# Processing_Unit.net
KiCad netlist of a schematic drawn in Altium Designer
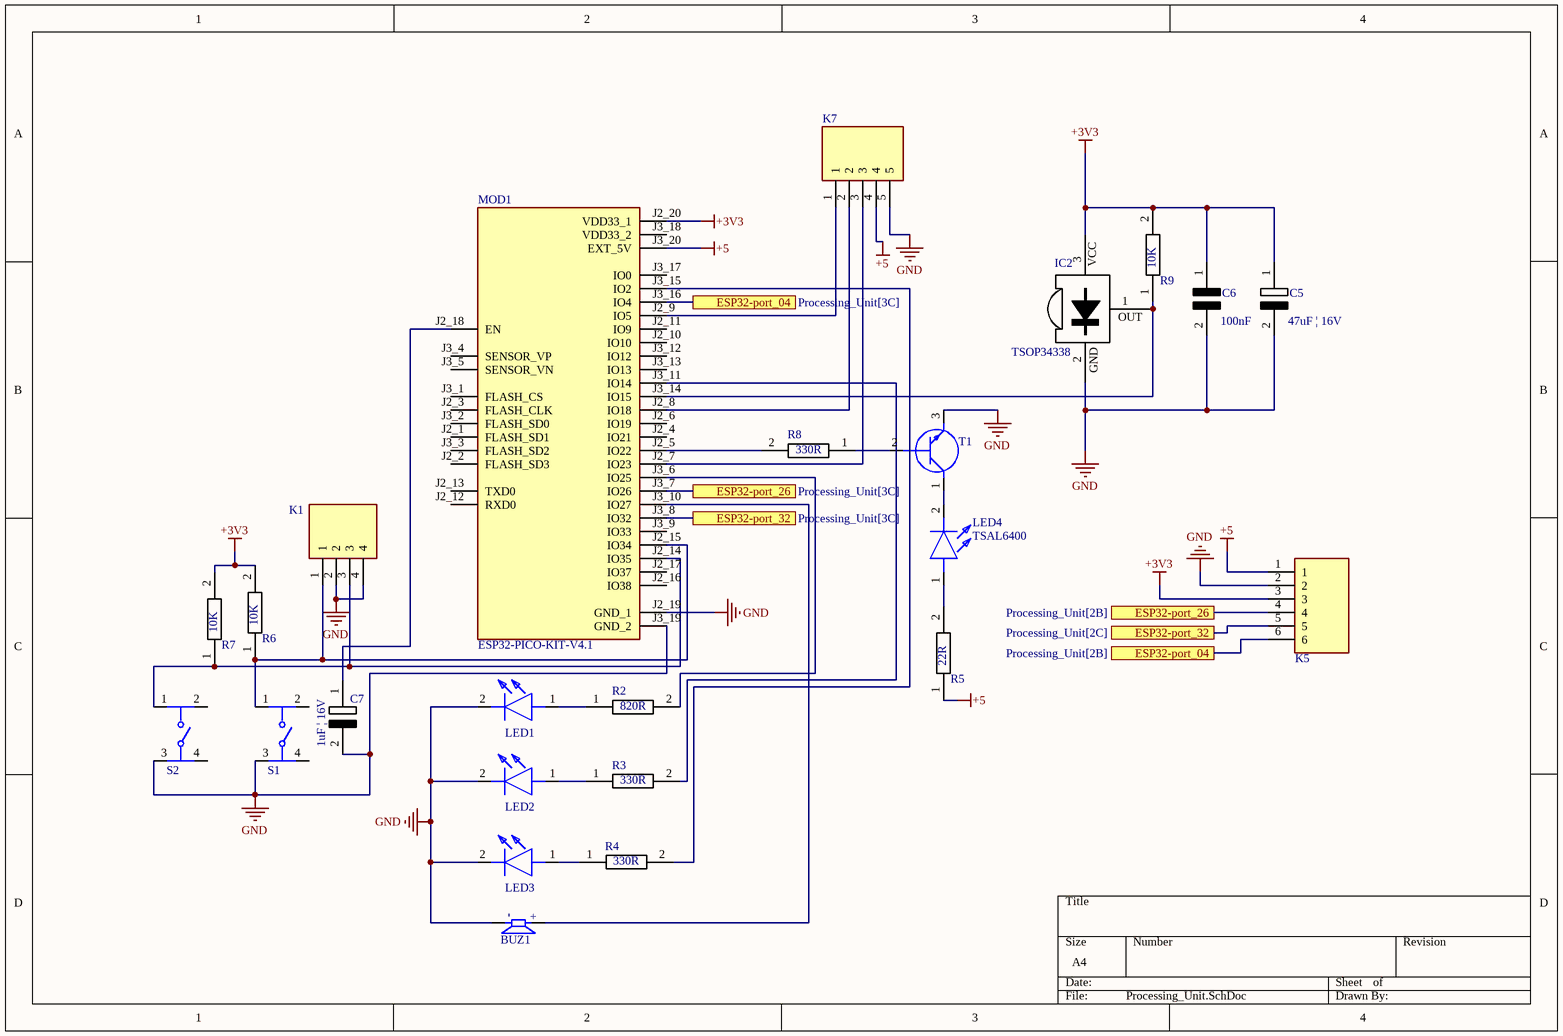
[diagram p0: Processing_Unit.SchDoc]

(export (version "E")
  (design (tool "Eeschema 10.0.6"))
  (components
    (comp (ref "BUZ1")
      (value "CEM-1212S")
      (footprint "CUI_CEM-1212S")
      (description "12 mm, 12 V, 85 dB, Through Hole, Sealed, Magnetic Audio Transducer Buzzer")
      (fields (field (name "MF") "CUI Devices"))
      (libsource (lib "Schlib1") (part "CEM-1212S"))
    )
    (comp (ref "C5")
      (value "47uF ¦ 16V")
      (footprint "C0805")
      (description "0805 ceramic capacitor")
      (fields
        (field (name "MANUFACTURER_PART_NUMBER") "GRM188R71H103KA01D")
        (field (name "MOUSER PART NUMBER") "81-GRM39X103K50D")
      )
      (libsource (lib "Schlib1") (part "elektrolytischeC0805"))
    )
    (comp (ref "C6")
      (value "100nF")
      (footprint "C0805")
      (description "0805 ceramic capacitor")
      (fields
        (field (name "MANUFACTURER_PART_NUMBER") "GRM188R71H103KA01D")
        (field (name "MOUSER PART NUMBER") "81-GRM39X103K50D")
      )
      (libsource (lib "Schlib1") (part "KeramischeC0805_1"))
    )
    (comp (ref "C7")
      (value "1uF ¦ 16V")
      (footprint "C0805")
      (description "0805 ceramic capacitor")
      (fields
        (field (name "MANUFACTURER_PART_NUMBER") "GRM188R71H103KA01D")
        (field (name "MOUSER PART NUMBER") "81-GRM39X103K50D")
      )
      (libsource (lib "Schlib1") (part "elektrolytischeC0805"))
    )
    (comp (ref "IC2")
      (value "TSOP34338")
      (footprint "TO_TSOP31236")
      (description "No Description Available")
      (libsource (lib "Schlib1") (part "TSOP34338"))
    )
    (comp (ref "K1")
      (value "2212S-04SG-85")
      (footprint "SamacSys:2212S04SG85")
      (description "Connector")
      (libsource (lib "Schlib1") (part "2212S-04SG-85"))
    )
    (comp (ref "K5")
      (value "2212S-06SG-85")
      (footprint "SamacSys:RHDR6W74P0X254_1X6_1574X250X850P")
      (description "Connector")
      (libsource (lib "Schlib1") (part "2212S-06SG-85"))
    )
    (comp (ref "K7")
      (value "2212S-05SG-85")
      (footprint "SamacSys:RHDR5W74P0X254_1X5_1320X250X850P")
      (description "Connector")
      (libsource (lib "Schlib1") (part "2212S-05SG-85"))
    )
    (comp (ref "LED1")
      (value "TLHO4200")
      (footprint "SamacSys:TLHO4200")
      (description "LED")
      (libsource (lib "Schlib1") (part "TLHO4200"))
    )
    (comp (ref "LED2")
      (value "TLHO4200")
      (footprint "SamacSys:TLHO4200")
      (description "LED")
      (libsource (lib "Schlib1") (part "TLHO4200"))
    )
    (comp (ref "LED3")
      (value "TLHO4200")
      (footprint "SamacSys:TLHO4200")
      (description "LED")
      (libsource (lib "Schlib1") (part "TLHO4200"))
    )
    (comp (ref "LED4")
      (value "TSAL6400")
      (footprint "SamacSys:TSAL6400")
      (description "LED")
      (fields (field (name "MOUSER PART NUMBER") "782-TSAL6400"))
      (libsource (lib "Schlib1") (part "TSAL6400"))
    )
    (comp (ref "MOD1")
      (value "ESP32-PICO-KIT-V4.1")
      (footprint "XCVR_ESP32-PICO-KIT-V4.1")
      (description "WiFi Development Tools (802.11)")
      (fields (field (name "MF") "Espressif Systems"))
      (libsource (lib "Schlib1") (part "ESP32-PICO-KIT-V4.1"))
    )
    (comp (ref "R2")
      (value "820R")
      (footprint "C0805")
      (description "Resistor0805")
      (fields
        (field (name "MANUFACTURER_PART_NUMBER") "CRCW08050000Z0EAHP")
        (field (name "MOUSER PART NUMBER") "71-CRCW08050000Z0EAH")
      )
      (libsource (lib "Schlib1") (part "Resistor0805"))
    )
    (comp (ref "R3")
      (value "330R")
      (footprint "C0805")
      (description "Resistor0805")
      (fields
        (field (name "MANUFACTURER_PART_NUMBER") "CRCW08050000Z0EAHP")
        (field (name "MOUSER PART NUMBER") "71-CRCW08050000Z0EAH")
      )
      (libsource (lib "Schlib1") (part "Resistor0805"))
    )
    (comp (ref "R4")
      (value "330R")
      (footprint "C0805")
      (description "Resistor0805")
      (fields
        (field (name "MANUFACTURER_PART_NUMBER") "CRCW08050000Z0EAHP")
        (field (name "MOUSER PART NUMBER") "71-CRCW08050000Z0EAH")
      )
      (libsource (lib "Schlib1") (part "Resistor0805"))
    )
    (comp (ref "R5")
      (value "22R")
      (footprint "C0805")
      (description "Resistor0805")
      (fields
        (field (name "MANUFACTURER_PART_NUMBER") "CRCW08050000Z0EAHP")
        (field (name "MOUSER PART NUMBER") "71-CRCW08050000Z0EAH")
      )
      (libsource (lib "Schlib1") (part "Resistor0805"))
    )
    (comp (ref "R6")
      (value "10K")
      (footprint "C0805")
      (description "Resistor0805")
      (fields
        (field (name "MANUFACTURER_PART_NUMBER") "CRCW08050000Z0EAHP")
        (field (name "MOUSER PART NUMBER") "71-CRCW08050000Z0EAH")
      )
      (libsource (lib "Schlib1") (part "Resistor0805"))
    )
    (comp (ref "R7")
      (value "10K")
      (footprint "C0805")
      (description "Resistor0805")
      (fields
        (field (name "MANUFACTURER_PART_NUMBER") "CRCW08050000Z0EAHP")
        (field (name "MOUSER PART NUMBER") "71-CRCW08050000Z0EAH")
      )
      (libsource (lib "Schlib1") (part "Resistor0805"))
    )
    (comp (ref "R8")
      (value "330R")
      (footprint "C0805")
      (description "Resistor0805")
      (fields
        (field (name "MANUFACTURER_PART_NUMBER") "CRCW08050000Z0EAHP")
        (field (name "MOUSER PART NUMBER") "71-CRCW08050000Z0EAH")
      )
      (libsource (lib "Schlib1") (part "Resistor0805"))
    )
    (comp (ref "R9")
      (value "10K")
      (footprint "C0805")
      (description "Resistor0805")
      (fields
        (field (name "MANUFACTURER_PART_NUMBER") "CRCW08050000Z0EAHP")
        (field (name "MOUSER PART NUMBER") "71-CRCW08050000Z0EAH")
      )
      (libsource (lib "Schlib1") (part "Resistor0805"))
    )
    (comp (ref "S1")
      (value "FSM103")
      (footprint "FP-FSM103-MFG")
      (description "SWITCH TACTILE SPST-NO 0.05A 24V")
      (libsource (lib "Schlib1") (part "CMP-03407-000037-1"))
    )
    (comp (ref "S2")
      (value "FSM103")
      (footprint "FP-FSM103-MFG")
      (description "SWITCH TACTILE SPST-NO 0.05A 24V")
      (libsource (lib "Schlib1") (part "CMP-03407-000037-1"))
    )
    (comp (ref "T1")
      (value "BC33716TA")
      (footprint "SamacSys:BC33716TA")
      (description "Transistor BJT NPN")
      (fields (field (name "MOUSER PART NUMBER") "512-BC33716TA"))
      (libsource (lib "Schlib1") (part "BC33716TA"))
    )
  )
  (nets
    (net (code "1") (name "+3V3") (class "Default")
      (node (ref "C5") (pin "1") (pinfunction "1_1") (pintype "passive"))
      (node (ref "C6") (pin "1") (pinfunction "1_1") (pintype "passive"))
      (node (ref "IC2") (pin "3") (pinfunction "VS_3") (pintype "power_in"))
      (node (ref "K5") (pin "3") (pinfunction "3_3") (pintype "passive"))
      (node (ref "MOD1") (pin "J2_20") (pinfunction "VDD33_1_J2_20") (pintype "passive"))
      (node (ref "R6") (pin "2") (pinfunction "2_2") (pintype "passive"))
      (node (ref "R7") (pin "2") (pinfunction "2_2") (pintype "passive"))
      (node (ref "R9") (pin "2") (pinfunction "2_2") (pintype "passive"))
    )
    (net (code "2") (name "+5") (class "Default")
      (node (ref "K5") (pin "1") (pinfunction "1_1") (pintype "passive"))
      (node (ref "K7") (pin "4") (pinfunction "4_4") (pintype "passive"))
      (node (ref "MOD1") (pin "J3_20") (pinfunction "EXT_5V_J3_20") (pintype "passive"))
      (node (ref "R5") (pin "1") (pinfunction "1_1") (pintype "passive"))
    )
    (net (code "3") (name "/ESP32-port_04") (class "Default")
      (node (ref "K5") (pin "6") (pinfunction "6_6") (pintype "passive"))
      (node (ref "MOD1") (pin "J3_16") (pinfunction "IO4_J3_16") (pintype "passive"))
    )
    (net (code "4") (name "/ESP32-port_26") (class "Default")
      (node (ref "K5") (pin "4") (pinfunction "4_4") (pintype "passive"))
      (node (ref "MOD1") (pin "J3_7") (pinfunction "IO26_J3_7") (pintype "passive"))
    )
    (net (code "5") (name "/ESP32-port_32") (class "Default")
      (node (ref "K5") (pin "5") (pinfunction "5_5") (pintype "passive"))
      (node (ref "MOD1") (pin "J3_8") (pinfunction "IO32_J3_8") (pintype "passive"))
    )
    (net (code "6") (name "GND") (class "Default")
      (node (ref "BUZ1") (pin "M") (pinfunction "M_M") (pintype "passive"))
      (node (ref "C5") (pin "2") (pinfunction "2_2") (pintype "passive"))
      (node (ref "C6") (pin "2") (pinfunction "2_2") (pintype "passive"))
      (node (ref "C7") (pin "2") (pinfunction "2_2") (pintype "passive"))
      (node (ref "IC2") (pin "2") (pinfunction "GND_2") (pintype "power_in"))
      (node (ref "K1") (pin "2") (pinfunction "2_2") (pintype "passive"))
      (node (ref "K1") (pin "4") (pinfunction "4_4") (pintype "passive"))
      (node (ref "K5") (pin "2") (pinfunction "2_2") (pintype "passive"))
      (node (ref "K7") (pin "5") (pinfunction "5_5") (pintype "passive"))
      (node (ref "LED1") (pin "2") (pinfunction "K_2") (pintype "passive"))
      (node (ref "LED2") (pin "2") (pinfunction "K_2") (pintype "passive"))
      (node (ref "LED3") (pin "2") (pinfunction "K_2") (pintype "passive"))
      (node (ref "MOD1") (pin "J2_19") (pinfunction "GND_1_J2_19") (pintype "passive"))
      (node (ref "MOD1") (pin "J3_19") (pinfunction "GND_2_J3_19") (pintype "passive"))
      (node (ref "S1") (pin "3") (pinfunction "3_3") (pintype "passive"))
      (node (ref "S2") (pin "3") (pinfunction "3_3") (pintype "passive"))
      (node (ref "T1") (pin "3") (pinfunction "E_3") (pintype "passive"))
    )
    (net (code "7") (name "Net-(IC2-OUT)") (class "Default")
      (node (ref "IC2") (pin "1") (pinfunction "OUT_1") (pintype "passive"))
      (node (ref "MOD1") (pin "J3_14") (pinfunction "IO15_J3_14") (pintype "passive"))
      (node (ref "R9") (pin "1") (pinfunction "1_1") (pintype "passive"))
    )
    (net (code "8") (name "Net-(LED1-A)") (class "Default")
      (node (ref "LED1") (pin "1") (pinfunction "A_1") (pintype "passive"))
      (node (ref "R2") (pin "1") (pinfunction "1_1") (pintype "passive"))
    )
    (net (code "9") (name "Net-(LED2-A)") (class "Default")
      (node (ref "LED2") (pin "1") (pinfunction "A_1") (pintype "passive"))
      (node (ref "R3") (pin "1") (pinfunction "1_1") (pintype "passive"))
    )
    (net (code "10") (name "Net-(LED3-A)") (class "Default")
      (node (ref "LED3") (pin "1") (pinfunction "A_1") (pintype "passive"))
      (node (ref "R4") (pin "1") (pinfunction "1_1") (pintype "passive"))
    )
    (net (code "11") (name "Net-(LED4-A)") (class "Default")
      (node (ref "LED4") (pin "1") (pinfunction "A_1") (pintype "passive"))
      (node (ref "R5") (pin "2") (pinfunction "2_2") (pintype "passive"))
    )
    (net (code "12") (name "Net-(LED4-K)") (class "Default")
      (node (ref "LED4") (pin "2") (pinfunction "K_2") (pintype "passive"))
      (node (ref "T1") (pin "1") (pinfunction "C_1") (pintype "passive"))
    )
    (net (code "13") (name "Net-(MOD1-EN)") (class "Default")
      (node (ref "C7") (pin "1") (pinfunction "1_1") (pintype "passive"))
      (node (ref "MOD1") (pin "J2_18") (pinfunction "EN_J2_18") (pintype "passive"))
    )
    (net (code "14") (name "Net-(MOD1-IO2)") (class "Default")
      (node (ref "MOD1") (pin "J3_15") (pinfunction "IO2_J3_15") (pintype "passive"))
      (node (ref "R4") (pin "2") (pinfunction "2_2") (pintype "passive"))
    )
    (net (code "15") (name "Net-(MOD1-IO5)") (class "Default")
      (node (ref "K7") (pin "1") (pinfunction "1_1") (pintype "passive"))
      (node (ref "MOD1") (pin "J2_9") (pinfunction "IO5_J2_9") (pintype "passive"))
    )
    (net (code "16") (name "Net-(MOD1-IO14)") (class "Default")
      (node (ref "MOD1") (pin "J3_11") (pinfunction "IO14_J3_11") (pintype "passive"))
      (node (ref "R3") (pin "2") (pinfunction "2_2") (pintype "passive"))
    )
    (net (code "17") (name "Net-(MOD1-IO18)") (class "Default")
      (node (ref "K7") (pin "2") (pinfunction "2_2") (pintype "passive"))
      (node (ref "MOD1") (pin "J2_8") (pinfunction "IO18_J2_8") (pintype "passive"))
    )
    (net (code "18") (name "Net-(MOD1-IO22)") (class "Default")
      (node (ref "MOD1") (pin "J2_5") (pinfunction "IO22_J2_5") (pintype "passive"))
      (node (ref "R8") (pin "2") (pinfunction "2_2") (pintype "passive"))
    )
    (net (code "19") (name "Net-(MOD1-IO23)") (class "Default")
      (node (ref "K7") (pin "3") (pinfunction "3_3") (pintype "passive"))
      (node (ref "MOD1") (pin "J2_7") (pinfunction "IO23_J2_7") (pintype "passive"))
    )
    (net (code "20") (name "Net-(MOD1-IO25)") (class "Default")
      (node (ref "MOD1") (pin "J3_6") (pinfunction "IO25_J3_6") (pintype "passive"))
      (node (ref "R2") (pin "2") (pinfunction "2_2") (pintype "passive"))
    )
    (net (code "21") (name "Net-(MOD1-IO27)") (class "Default")
      (node (ref "BUZ1") (pin "P") (pinfunction "P_P") (pintype "passive"))
      (node (ref "MOD1") (pin "J3_10") (pinfunction "IO27_J3_10") (pintype "passive"))
    )
    (net (code "22") (name "Net-(MOD1-IO34)") (class "Default")
      (node (ref "K1") (pin "1") (pinfunction "1_1") (pintype "passive"))
      (node (ref "MOD1") (pin "J2_15") (pinfunction "IO34_J2_15") (pintype "passive"))
      (node (ref "R6") (pin "1") (pinfunction "1_1") (pintype "passive"))
      (node (ref "S1") (pin "1") (pinfunction "1_1") (pintype "passive"))
    )
    (net (code "23") (name "Net-(MOD1-IO35)") (class "Default")
      (node (ref "K1") (pin "3") (pinfunction "3_3") (pintype "passive"))
      (node (ref "MOD1") (pin "J2_14") (pinfunction "IO35_J2_14") (pintype "passive"))
      (node (ref "R7") (pin "1") (pinfunction "1_1") (pintype "passive"))
      (node (ref "S2") (pin "1") (pinfunction "1_1") (pintype "passive"))
    )
    (net (code "24") (name "Net-(T1-B)") (class "Default")
      (node (ref "R8") (pin "1") (pinfunction "1_1") (pintype "passive"))
      (node (ref "T1") (pin "2") (pinfunction "B_2") (pintype "passive"))
    )
    (net (code "25") (name "unconnected-(MOD1-FLASH_CLK-PadJ2_3)") (class "Default")
      (node (ref "MOD1") (pin "J2_3") (pinfunction "FLASH_CLK_J2_3") (pintype "passive"))
    )
    (net (code "26") (name "unconnected-(MOD1-FLASH_CS-PadJ3_1)") (class "Default")
      (node (ref "MOD1") (pin "J3_1") (pinfunction "FLASH_CS_J3_1") (pintype "passive"))
    )
    (net (code "27") (name "unconnected-(MOD1-FLASH_SD0-PadJ3_2)") (class "Default")
      (node (ref "MOD1") (pin "J3_2") (pinfunction "FLASH_SD0_J3_2") (pintype "passive"))
    )
    (net (code "28") (name "unconnected-(MOD1-FLASH_SD1-PadJ2_1)") (class "Default")
      (node (ref "MOD1") (pin "J2_1") (pinfunction "FLASH_SD1_J2_1") (pintype "passive"))
    )
    (net (code "29") (name "unconnected-(MOD1-FLASH_SD2-PadJ3_3)") (class "Default")
      (node (ref "MOD1") (pin "J3_3") (pinfunction "FLASH_SD2_J3_3") (pintype "passive"))
    )
    (net (code "30") (name "unconnected-(MOD1-FLASH_SD3-PadJ2_2)") (class "Default")
      (node (ref "MOD1") (pin "J2_2") (pinfunction "FLASH_SD3_J2_2") (pintype "passive"))
    )
    (net (code "31") (name "unconnected-(MOD1-IO0-PadJ3_17)") (class "Default")
      (node (ref "MOD1") (pin "J3_17") (pinfunction "IO0_J3_17") (pintype "passive"))
    )
    (net (code "32") (name "unconnected-(MOD1-IO9-PadJ2_11)") (class "Default")
      (node (ref "MOD1") (pin "J2_11") (pinfunction "IO9_J2_11") (pintype "passive"))
    )
    (net (code "33") (name "unconnected-(MOD1-IO10-PadJ2_10)") (class "Default")
      (node (ref "MOD1") (pin "J2_10") (pinfunction "IO10_J2_10") (pintype "passive"))
    )
    (net (code "34") (name "unconnected-(MOD1-IO12-PadJ3_12)") (class "Default")
      (node (ref "MOD1") (pin "J3_12") (pinfunction "IO12_J3_12") (pintype "passive"))
    )
    (net (code "35") (name "unconnected-(MOD1-IO13-PadJ3_13)") (class "Default")
      (node (ref "MOD1") (pin "J3_13") (pinfunction "IO13_J3_13") (pintype "passive"))
    )
    (net (code "36") (name "unconnected-(MOD1-IO19-PadJ2_6)") (class "Default")
      (node (ref "MOD1") (pin "J2_6") (pinfunction "IO19_J2_6") (pintype "passive"))
    )
    (net (code "37") (name "unconnected-(MOD1-IO21-PadJ2_4)") (class "Default")
      (node (ref "MOD1") (pin "J2_4") (pinfunction "IO21_J2_4") (pintype "passive"))
    )
    (net (code "38") (name "unconnected-(MOD1-IO33-PadJ3_9)") (class "Default")
      (node (ref "MOD1") (pin "J3_9") (pinfunction "IO33_J3_9") (pintype "passive"))
    )
    (net (code "39") (name "unconnected-(MOD1-IO37-PadJ2_17)") (class "Default")
      (node (ref "MOD1") (pin "J2_17") (pinfunction "IO37_J2_17") (pintype "passive"))
    )
    (net (code "40") (name "unconnected-(MOD1-IO38-PadJ2_16)") (class "Default")
      (node (ref "MOD1") (pin "J2_16") (pinfunction "IO38_J2_16") (pintype "passive"))
    )
    (net (code "41") (name "unconnected-(MOD1-RXD0-PadJ2_12)") (class "Default")
      (node (ref "MOD1") (pin "J2_12") (pinfunction "RXD0_J2_12") (pintype "passive"))
    )
    (net (code "42") (name "unconnected-(MOD1-SENSOR_VN-PadJ3_5)") (class "Default")
      (node (ref "MOD1") (pin "J3_5") (pinfunction "SENSOR_VN_J3_5") (pintype "passive"))
    )
    (net (code "43") (name "unconnected-(MOD1-SENSOR_VP-PadJ3_4)") (class "Default")
      (node (ref "MOD1") (pin "J3_4") (pinfunction "SENSOR_VP_J3_4") (pintype "passive"))
    )
    (net (code "44") (name "unconnected-(MOD1-TXD0-PadJ2_13)") (class "Default")
      (node (ref "MOD1") (pin "J2_13") (pinfunction "TXD0_J2_13") (pintype "passive"))
    )
    (net (code "45") (name "unconnected-(MOD1-VDD33_2-PadJ3_18)") (class "Default")
      (node (ref "MOD1") (pin "J3_18") (pinfunction "VDD33_2_J3_18") (pintype "passive"))
    )
    (net (code "46") (name "unconnected-(S1-Pad2)") (class "Default")
      (node (ref "S1") (pin "2") (pinfunction "2_2") (pintype "passive"))
    )
    (net (code "47") (name "unconnected-(S1-Pad4)") (class "Default")
      (node (ref "S1") (pin "4") (pinfunction "4_4") (pintype "passive"))
    )
    (net (code "48") (name "unconnected-(S2-Pad2)") (class "Default")
      (node (ref "S2") (pin "2") (pinfunction "2_2") (pintype "passive"))
    )
    (net (code "49") (name "unconnected-(S2-Pad4)") (class "Default")
      (node (ref "S2") (pin "4") (pinfunction "4_4") (pintype "passive"))
    )
  )
)
